# PDB_v0.net
KiCad netlist of a schematic drawn in EAGLE
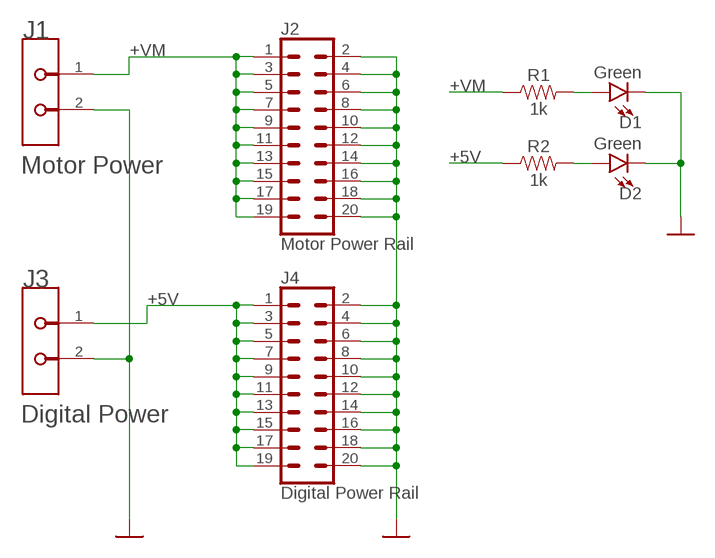
[diagram p0: schematic, sheet 1]

(export (version "E")
  (design (tool "Eeschema 10.0.6"))
  (components
    (comp (ref "D1")
      (value "Green")
      (footprint "eagle-import:LED_3MM")
      (libsource (lib "eagle-import") (part "LED3MM"))
    )
    (comp (ref "D2")
      (value "Green")
      (footprint "eagle-import:LED_3MM")
      (libsource (lib "eagle-import") (part "LED3MM"))
    )
    (comp (ref "J1")
      (value "Motor Power")
      (footprint "eagle-import:TE_282837-2_0")
      (fields
        (field (name "DIGIKEY_PART_NUMBER") "A113320-ND")
        (field (name "MF") "TE")
        (field (name "MOUSER_PART_NUMBER") "571-2828372")
      )
      (libsource (lib "eagle-import") (part "TE_282837-2TE_282837-2_0_0"))
    )
    (comp (ref "J2")
      (value "Motor Power Rail")
      (footprint "eagle-import:2X10")
      (libsource (lib "eagle-import") (part "CONN_10X2"))
    )
    (comp (ref "J3")
      (value "Digital Power")
      (footprint "eagle-import:TE_282837-2_0")
      (fields
        (field (name "DIGIKEY_PART_NUMBER") "A113320-ND")
        (field (name "MF") "TE")
        (field (name "MOUSER_PART_NUMBER") "571-2828372")
      )
      (libsource (lib "eagle-import") (part "TE_282837-2TE_282837-2_0_0"))
    )
    (comp (ref "J4")
      (value "Digital Power Rail")
      (footprint "eagle-import:2X10")
      (libsource (lib "eagle-import") (part "CONN_10X2"))
    )
    (comp (ref "R1")
      (value "1k")
      (footprint "eagle-import:AXIAL-0.3")
      (libsource (lib "eagle-import") (part "RESISTORAXIAL-0.3"))
    )
    (comp (ref "R2")
      (value "1k")
      (footprint "eagle-import:AXIAL-0.3")
      (libsource (lib "eagle-import") (part "RESISTORAXIAL-0.3"))
    )
  )
  (nets
    (net (code "1") (name "/+5V") (class "Default")
      (node (ref "J3") (pin "1") (pinfunction "1_1") (pintype "passive"))
      (node (ref "J4") (pin "1") (pinfunction "1_1") (pintype "passive"))
      (node (ref "J4") (pin "11") (pinfunction "11_11") (pintype "passive"))
      (node (ref "J4") (pin "13") (pinfunction "13_13") (pintype "passive"))
      (node (ref "J4") (pin "15") (pinfunction "15_15") (pintype "passive"))
      (node (ref "J4") (pin "17") (pinfunction "17_17") (pintype "passive"))
      (node (ref "J4") (pin "19") (pinfunction "19_19") (pintype "passive"))
      (node (ref "J4") (pin "3") (pinfunction "3_3") (pintype "passive"))
      (node (ref "J4") (pin "5") (pinfunction "5_5") (pintype "passive"))
      (node (ref "J4") (pin "7") (pinfunction "7_7") (pintype "passive"))
      (node (ref "J4") (pin "9") (pinfunction "9_9") (pintype "passive"))
      (node (ref "R2") (pin "P$1") (pinfunction "1_P$1") (pintype "passive"))
    )
    (net (code "2") (name "/+VM") (class "Default")
      (node (ref "J1") (pin "1") (pinfunction "1_1") (pintype "passive"))
      (node (ref "J2") (pin "1") (pinfunction "1_1") (pintype "passive"))
      (node (ref "J2") (pin "11") (pinfunction "11_11") (pintype "passive"))
      (node (ref "J2") (pin "13") (pinfunction "13_13") (pintype "passive"))
      (node (ref "J2") (pin "15") (pinfunction "15_15") (pintype "passive"))
      (node (ref "J2") (pin "17") (pinfunction "17_17") (pintype "passive"))
      (node (ref "J2") (pin "19") (pinfunction "19_19") (pintype "passive"))
      (node (ref "J2") (pin "3") (pinfunction "3_3") (pintype "passive"))
      (node (ref "J2") (pin "5") (pinfunction "5_5") (pintype "passive"))
      (node (ref "J2") (pin "7") (pinfunction "7_7") (pintype "passive"))
      (node (ref "J2") (pin "9") (pinfunction "9_9") (pintype "passive"))
      (node (ref "R1") (pin "P$1") (pinfunction "1_P$1") (pintype "passive"))
    )
    (net (code "3") (name "DGND") (class "Default")
      (node (ref "D1") (pin "K") (pinfunction "C_K") (pintype "passive"))
      (node (ref "D2") (pin "K") (pinfunction "C_K") (pintype "passive"))
      (node (ref "J1") (pin "2") (pinfunction "2_2") (pintype "passive"))
      (node (ref "J2") (pin "10") (pinfunction "10_10") (pintype "passive"))
      (node (ref "J2") (pin "12") (pinfunction "12_12") (pintype "passive"))
      (node (ref "J2") (pin "14") (pinfunction "14_14") (pintype "passive"))
      (node (ref "J2") (pin "16") (pinfunction "16_16") (pintype "passive"))
      (node (ref "J2") (pin "18") (pinfunction "18_18") (pintype "passive"))
      (node (ref "J2") (pin "2") (pinfunction "2_2") (pintype "passive"))
      (node (ref "J2") (pin "20") (pinfunction "20_20") (pintype "passive"))
      (node (ref "J2") (pin "4") (pinfunction "4_4") (pintype "passive"))
      (node (ref "J2") (pin "6") (pinfunction "6_6") (pintype "passive"))
      (node (ref "J2") (pin "8") (pinfunction "8_8") (pintype "passive"))
      (node (ref "J3") (pin "2") (pinfunction "2_2") (pintype "passive"))
      (node (ref "J4") (pin "10") (pinfunction "10_10") (pintype "passive"))
      (node (ref "J4") (pin "12") (pinfunction "12_12") (pintype "passive"))
      (node (ref "J4") (pin "14") (pinfunction "14_14") (pintype "passive"))
      (node (ref "J4") (pin "16") (pinfunction "16_16") (pintype "passive"))
      (node (ref "J4") (pin "18") (pinfunction "18_18") (pintype "passive"))
      (node (ref "J4") (pin "2") (pinfunction "2_2") (pintype "passive"))
      (node (ref "J4") (pin "20") (pinfunction "20_20") (pintype "passive"))
      (node (ref "J4") (pin "4") (pinfunction "4_4") (pintype "passive"))
      (node (ref "J4") (pin "6") (pinfunction "6_6") (pintype "passive"))
      (node (ref "J4") (pin "8") (pinfunction "8_8") (pintype "passive"))
    )
    (net (code "4") (name "Net-(R1-2)") (class "Default")
      (node (ref "D1") (pin "A") (pinfunction "A_A") (pintype "passive"))
      (node (ref "R1") (pin "P$2") (pinfunction "2_P$2") (pintype "passive"))
    )
    (net (code "5") (name "Net-(R2-2)") (class "Default")
      (node (ref "D2") (pin "A") (pinfunction "A_A") (pintype "passive"))
      (node (ref "R2") (pin "P$2") (pinfunction "2_P$2") (pintype "passive"))
    )
  )
)
